# AMPLIFIER.net
KiCad netlist of a schematic drawn in Altium Designer
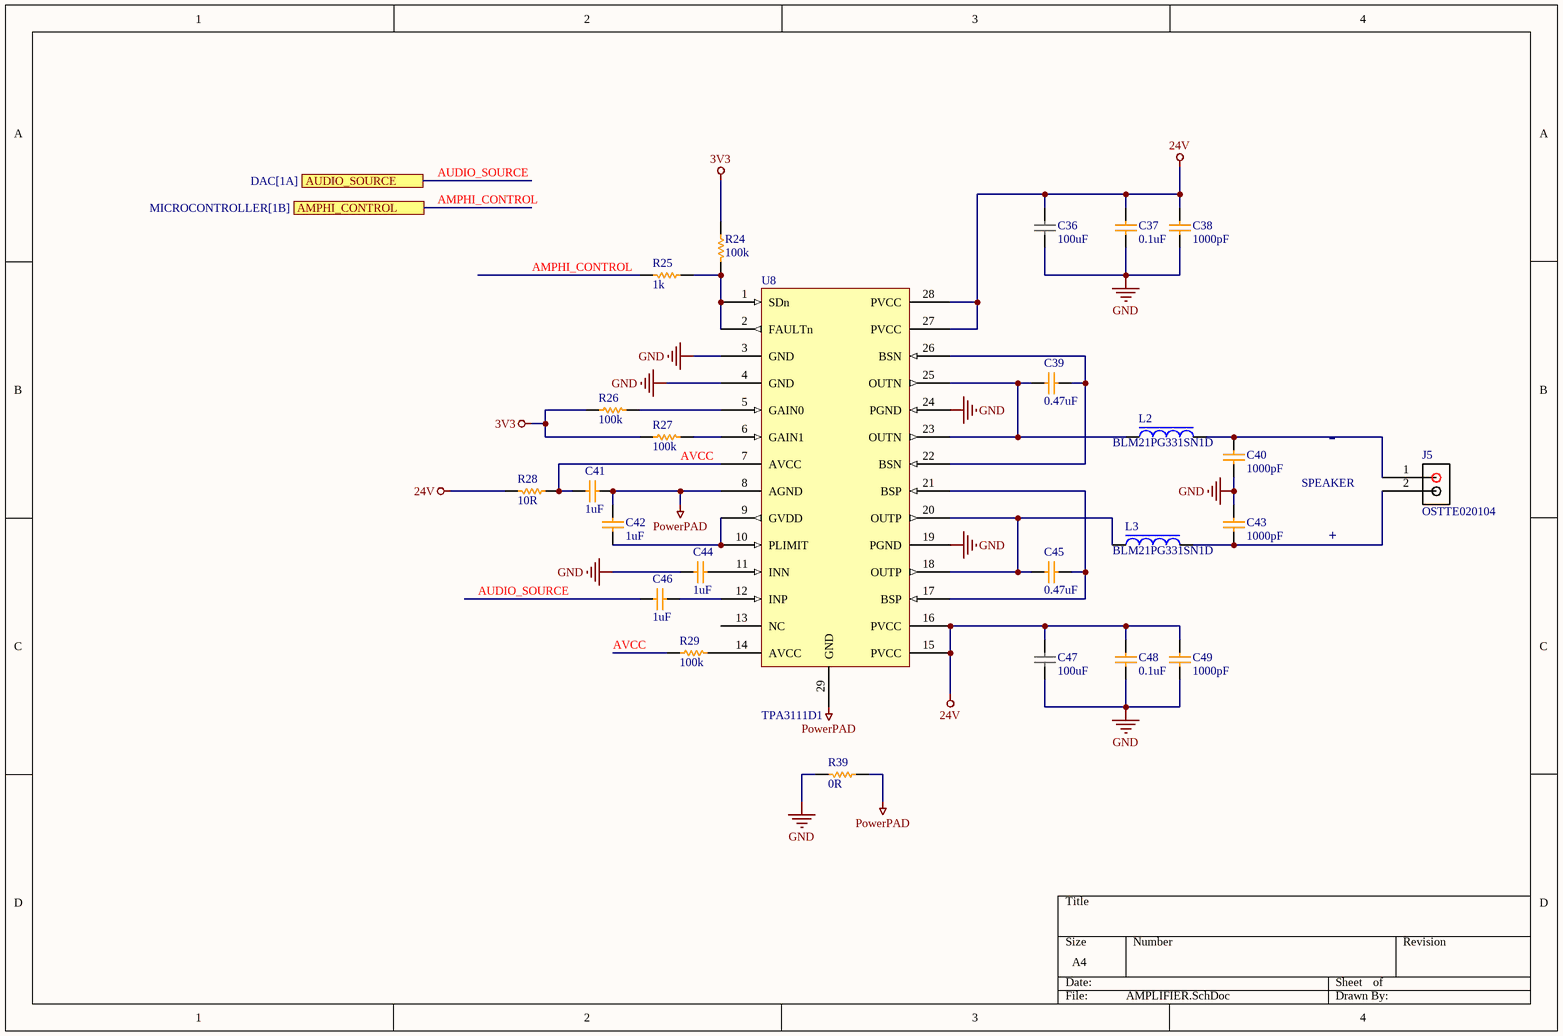
[diagram p0: AMPLIFIER.SchDoc]

(export (version "E")
  (design (tool "Eeschema 10.0.6"))
  (components
    (comp (ref "C36")
      (value "100uF")
      (footprint "CAP-SMD-10x10")
      (description "CAP ALUM 100UF 20% 50V SMD(UUQ1H101MCL1GS)")
      (libsource (lib "Schlib1") (part "CAP-SMD-ALUM"))
    )
    (comp (ref "C37")
      (value "0.1uF")
      (footprint "CAP-0603")
      (description "CAP CER 0.1UF 50V X7R 0805")
      (libsource (lib "Schlib1") (part "CAP-0603"))
    )
    (comp (ref "C38")
      (value "1000pF")
      (footprint "CAP-0603")
      (description "CAP CER 1000PF 50V X7R 0603")
      (libsource (lib "Schlib1") (part "CAP-0603"))
    )
    (comp (ref "C39")
      (value "0.47uF")
      (footprint "CAP-0603")
      (description "CAP CER 0.47UF 50V X7R 0805")
      (libsource (lib "Schlib1") (part "CAP-0603"))
    )
    (comp (ref "C40")
      (value "1000pF")
      (footprint "CAP-0603")
      (description "CAP CER 1000PF 50V X7R 0603")
      (libsource (lib "Schlib1") (part "CAP-0603"))
    )
    (comp (ref "C41")
      (value "1uF")
      (footprint "CAP-0603")
      (description "CAP CER 1UF 25V X7R 0603")
      (libsource (lib "Schlib1") (part "CAP-0603"))
    )
    (comp (ref "C42")
      (value "1uF")
      (footprint "CAP-0603")
      (description "CAP CER 1UF 25V X7R 0603")
      (libsource (lib "Schlib1") (part "CAP-0603"))
    )
    (comp (ref "C43")
      (value "1000pF")
      (footprint "CAP-0603")
      (description "CAP CER 1000PF 50V X7R 0603")
      (libsource (lib "Schlib1") (part "CAP-0603"))
    )
    (comp (ref "C44")
      (value "1uF")
      (footprint "CAP-0603")
      (description "CAP CER 1UF 25V X7R 0603")
      (libsource (lib "Schlib1") (part "CAP-0603"))
    )
    (comp (ref "C45")
      (value "0.47uF")
      (footprint "CAP-0603")
      (description "CAP CER 0.47UF 50V X7R 0805")
      (libsource (lib "Schlib1") (part "CAP-0603"))
    )
    (comp (ref "C46")
      (value "1uF")
      (footprint "CAP-0603")
      (description "CAP CER 1UF 25V X7R 0603")
      (libsource (lib "Schlib1") (part "CAP-0603"))
    )
    (comp (ref "C47")
      (value "100uF")
      (footprint "CAP-SMD-10x10")
      (description "CAP ALUM 100UF 20% 50V SMD(UUQ1H101MCL1GS)")
      (libsource (lib "Schlib1") (part "CAP-SMD-ALUM"))
    )
    (comp (ref "C48")
      (value "0.1uF")
      (footprint "CAP-0603")
      (description "CAP CER 0.1UF 50V X7R 0805")
      (libsource (lib "Schlib1") (part "CAP-0603"))
    )
    (comp (ref "C49")
      (value "1000pF")
      (footprint "CAP-0603")
      (description "CAP CER 1000PF 50V X7R 0603")
      (libsource (lib "Schlib1") (part "CAP-0603"))
    )
    (comp (ref "J5")
      (value "OSTTE020104")
      (footprint "TERMBLK-P3.5-SIDEENT")
      (description "TERM BLK 2POS SIDE ENT 3.5MM PCB")
      (libsource (lib "schematic") (part "OSTTE020104"))
    )
    (comp (ref "L2")
      (value "BLM21PG331SN1D")
      (footprint "FB-0805")
      (description "FERRITE BEAD 330 OHM 0805 1LN")
      (libsource (lib "schematic") (part "FB-0805"))
    )
    (comp (ref "L3")
      (value "BLM21PG331SN1D")
      (footprint "FB-0805")
      (description "FERRITE BEAD 330 OHM 0805 1LN")
      (libsource (lib "schematic") (part "FB-0805"))
    )
    (comp (ref "R24")
      (value "100k")
      (footprint "RES-0603")
      (description "RES SMD 100K OHM 1% 1/10W 0603")
      (libsource (lib "Schlib1") (part "RES-0603"))
    )
    (comp (ref "R25")
      (value "1k")
      (footprint "RES-0603")
      (description "RES SMD 1K OHM 1% 1/10W 0603")
      (libsource (lib "Schlib1") (part "RES-0603"))
    )
    (comp (ref "R26")
      (value "100k")
      (footprint "RES-0603")
      (description "RES SMD 100K OHM 1% 1/10W 0603")
      (libsource (lib "Schlib1") (part "RES-0603"))
    )
    (comp (ref "R27")
      (value "100k")
      (footprint "RES-0603")
      (description "RES SMD 100K OHM 1% 1/10W 0603")
      (libsource (lib "Schlib1") (part "RES-0603"))
    )
    (comp (ref "R28")
      (value "10R")
      (footprint "RES-0603")
      (description "RES SMD 10 OHM 1% 1/10W 0603")
      (libsource (lib "Schlib1") (part "RES-0603"))
    )
    (comp (ref "R29")
      (value "100k")
      (footprint "RES-0603")
      (description "RES SMD 100K OHM 1% 1/10W 0603")
      (libsource (lib "Schlib1") (part "RES-0603"))
    )
    (comp (ref "R39")
      (value "0R")
      (footprint "RES-0603")
      (description "RES SMD 0 OHM 1% 1/10W 0603")
      (libsource (lib "Schlib1") (part "RES-0603"))
    )
    (comp (ref "U8")
      (value "TPA3111D1")
      (footprint "28HTSSOP")
      (description "IC AMP CLASS D MONO 10W 28HTSSOP")
      (libsource (lib "schematic") (part "TPA3111D1"))
    )
  )
  (nets
    (net (code "1") (name "/AMPHI_CONTROL") (class "Default")
      (node (ref "R25") (pin "1") (pinfunction "1_1") (pintype "passive"))
    )
    (net (code "2") (name "/AUDIO_SOURCE") (class "Default")
      (node (ref "C46") (pin "1") (pinfunction "1_1") (pintype "passive"))
    )
    (net (code "3") (name "/AVCC") (class "Default")
      (node (ref "C41") (pin "1") (pinfunction "1_1") (pintype "passive"))
      (node (ref "R28") (pin "2") (pinfunction "2_2") (pintype "passive"))
      (node (ref "R29") (pin "2") (pinfunction "2_2") (pintype "passive"))
      (node (ref "U8") (pin "7") (pinfunction "AVCC_7") (pintype "power_in"))
    )
    (net (code "4") (name "3V3") (class "Default")
      (node (ref "R24") (pin "2") (pinfunction "2_2") (pintype "passive"))
      (node (ref "R26") (pin "2") (pinfunction "2_2") (pintype "passive"))
      (node (ref "R27") (pin "2") (pinfunction "2_2") (pintype "passive"))
    )
    (net (code "5") (name "24V") (class "Default")
      (node (ref "C36") (pin "1") (pinfunction "1_1") (pintype "passive"))
      (node (ref "C37") (pin "2") (pinfunction "2_2") (pintype "passive"))
      (node (ref "C38") (pin "2") (pinfunction "2_2") (pintype "passive"))
      (node (ref "C47") (pin "1") (pinfunction "1_1") (pintype "passive"))
      (node (ref "C48") (pin "2") (pinfunction "2_2") (pintype "passive"))
      (node (ref "C49") (pin "2") (pinfunction "2_2") (pintype "passive"))
      (node (ref "R28") (pin "1") (pinfunction "1_1") (pintype "passive"))
      (node (ref "U8") (pin "15") (pinfunction "PVCC_15") (pintype "power_in"))
      (node (ref "U8") (pin "16") (pinfunction "PVCC_16") (pintype "power_in"))
      (node (ref "U8") (pin "27") (pinfunction "PVCC_27") (pintype "power_in"))
      (node (ref "U8") (pin "28") (pinfunction "PVCC_28") (pintype "power_in"))
    )
    (net (code "6") (name "GND") (class "Default")
      (node (ref "C36") (pin "2") (pinfunction "2_2") (pintype "passive"))
      (node (ref "C37") (pin "1") (pinfunction "1_1") (pintype "passive"))
      (node (ref "C38") (pin "1") (pinfunction "1_1") (pintype "passive"))
      (node (ref "C40") (pin "1") (pinfunction "1_1") (pintype "passive"))
      (node (ref "C43") (pin "2") (pinfunction "2_2") (pintype "passive"))
      (node (ref "C44") (pin "1") (pinfunction "1_1") (pintype "passive"))
      (node (ref "C47") (pin "2") (pinfunction "2_2") (pintype "passive"))
      (node (ref "C48") (pin "1") (pinfunction "1_1") (pintype "passive"))
      (node (ref "C49") (pin "1") (pinfunction "1_1") (pintype "passive"))
      (node (ref "R39") (pin "1") (pinfunction "1_1") (pintype "passive"))
      (node (ref "U8") (pin "19") (pinfunction "PGND_19") (pintype "passive"))
      (node (ref "U8") (pin "24") (pinfunction "PGND_24") (pintype "input"))
      (node (ref "U8") (pin "3") (pinfunction "GND_3") (pintype "passive"))
      (node (ref "U8") (pin "4") (pinfunction "GND_4") (pintype "passive"))
    )
    (net (code "7") (name "Net-(C39-Pad1)") (class "Default")
      (node (ref "C39") (pin "1") (pinfunction "1_1") (pintype "passive"))
      (node (ref "L2") (pin "1") (pinfunction "1_1") (pintype "passive"))
      (node (ref "U8") (pin "23") (pinfunction "OUTN_23") (pintype "output"))
      (node (ref "U8") (pin "25") (pinfunction "OUTN_25") (pintype "output"))
    )
    (net (code "8") (name "Net-(C39-Pad2)") (class "Default")
      (node (ref "C39") (pin "2") (pinfunction "2_2") (pintype "passive"))
      (node (ref "U8") (pin "22") (pinfunction "BSN_22") (pintype "input"))
      (node (ref "U8") (pin "26") (pinfunction "BSN_26") (pintype "input"))
    )
    (net (code "9") (name "Net-(C40-Pad2)") (class "Default")
      (node (ref "C40") (pin "2") (pinfunction "2_2") (pintype "passive"))
      (node (ref "J5") (pin "1") (pinfunction "2_1") (pintype "power_in"))
      (node (ref "L2") (pin "2") (pinfunction "2_2") (pintype "passive"))
    )
    (net (code "10") (name "Net-(C43-Pad1)") (class "Default")
      (node (ref "C43") (pin "1") (pinfunction "1_1") (pintype "passive"))
      (node (ref "J5") (pin "2") (pinfunction "2_2") (pintype "passive"))
      (node (ref "L3") (pin "2") (pinfunction "2_2") (pintype "passive"))
    )
    (net (code "11") (name "Net-(C45-Pad1)") (class "Default")
      (node (ref "C45") (pin "1") (pinfunction "1_1") (pintype "passive"))
      (node (ref "L3") (pin "1") (pinfunction "1_1") (pintype "passive"))
      (node (ref "U8") (pin "18") (pinfunction "OUTP_18") (pintype "output"))
      (node (ref "U8") (pin "20") (pinfunction "OUTP_20") (pintype "output"))
    )
    (net (code "12") (name "Net-(C45-Pad2)") (class "Default")
      (node (ref "C45") (pin "2") (pinfunction "2_2") (pintype "passive"))
      (node (ref "U8") (pin "17") (pinfunction "BSP_17") (pintype "input"))
      (node (ref "U8") (pin "21") (pinfunction "BSP_21") (pintype "input"))
    )
    (net (code "13") (name "Net-(R29-Pad1)") (class "Default")
      (node (ref "R29") (pin "1") (pinfunction "1_1") (pintype "passive"))
      (node (ref "U8") (pin "14") (pinfunction "AVCC_14") (pintype "power_in"))
    )
    (net (code "14") (name "Net-(U8-FAULTn)") (class "Default")
      (node (ref "R24") (pin "1") (pinfunction "1_1") (pintype "passive"))
      (node (ref "R25") (pin "2") (pinfunction "2_2") (pintype "passive"))
      (node (ref "U8") (pin "1") (pinfunction "SDn_1") (pintype "input"))
      (node (ref "U8") (pin "2") (pinfunction "FAULTn_2") (pintype "output"))
    )
    (net (code "15") (name "Net-(U8-GAIN0)") (class "Default")
      (node (ref "R26") (pin "1") (pinfunction "1_1") (pintype "passive"))
      (node (ref "U8") (pin "5") (pinfunction "GAIN0_5") (pintype "input"))
    )
    (net (code "16") (name "Net-(U8-GAIN1)") (class "Default")
      (node (ref "R27") (pin "1") (pinfunction "1_1") (pintype "passive"))
      (node (ref "U8") (pin "6") (pinfunction "GAIN1_6") (pintype "input"))
    )
    (net (code "17") (name "Net-(U8-GVDD)") (class "Default")
      (node (ref "C42") (pin "1") (pinfunction "1_1") (pintype "passive"))
      (node (ref "U8") (pin "10") (pinfunction "PLIMIT_10") (pintype "input"))
      (node (ref "U8") (pin "9") (pinfunction "GVDD_9") (pintype "output"))
    )
    (net (code "18") (name "Net-(U8-INN)") (class "Default")
      (node (ref "C44") (pin "2") (pinfunction "2_2") (pintype "passive"))
      (node (ref "U8") (pin "11") (pinfunction "INN_11") (pintype "input"))
    )
    (net (code "19") (name "Net-(U8-INP)") (class "Default")
      (node (ref "C46") (pin "2") (pinfunction "2_2") (pintype "passive"))
      (node (ref "U8") (pin "12") (pinfunction "INP_12") (pintype "input"))
    )
    (net (code "20") (name "PowerPAD") (class "Default")
      (node (ref "C41") (pin "2") (pinfunction "2_2") (pintype "passive"))
      (node (ref "C42") (pin "2") (pinfunction "2_2") (pintype "passive"))
      (node (ref "R39") (pin "2") (pinfunction "2_2") (pintype "passive"))
      (node (ref "U8") (pin "29") (pinfunction "GND_29") (pintype "passive"))
      (node (ref "U8") (pin "8") (pinfunction "AGND_8") (pintype "passive"))
    )
    (net (code "21") (name "unconnected-(U8-NC-Pad13)") (class "Default")
      (node (ref "U8") (pin "13") (pinfunction "NC_13") (pintype "passive"))
    )
  )
)
